# PWR-ORing_IC_2V_to_5V.net
KiCad netlist of a schematic drawn in Altium Designer
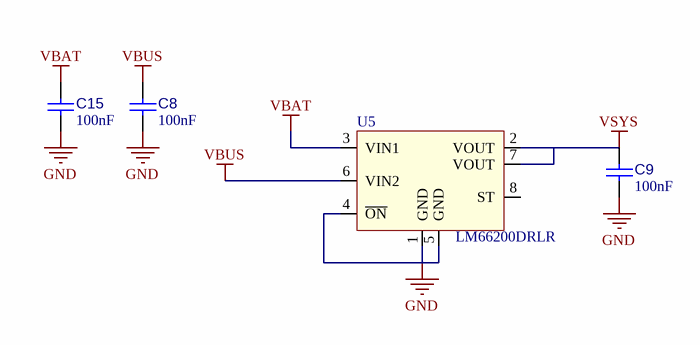
[diagram p0: PWR-ORing IC 2V to 5V.SchDoc]

(export (version "E")
  (design (tool "Eeschema 10.0.6"))
  (components
    (comp (ref "C8")
      (value "100nF")
      (footprint "C_1005[0402]")
      (description "Capacitor type 1")
      (fields (field (name "TOLERANCE") "10%") (field (name "Comment") "Cap 100nF 0402"))
      (libsource (lib "TEP_243-Altium_DBLib") (part "capacitor"))
    )
    (comp (ref "C9")
      (value "100nF")
      (footprint "C_1005[0402]")
      (description "Capacitor type 1")
      (fields (field (name "TOLERANCE") "10%") (field (name "Comment") "Cap 100nF 0402"))
      (libsource (lib "TEP_243-Altium_DBLib") (part "capacitor"))
    )
    (comp (ref "C15")
      (value "100nF")
      (footprint "C_1005[0402]")
      (description "Capacitor type 1")
      (fields (field (name "TOLERANCE") "10%") (field (name "Comment") "Cap 100nF 0402"))
      (libsource (lib "TEP_243-Altium_DBLib") (part "capacitor"))
    )
    (comp (ref "U5")
      (value "LM66200DRLR")
      (footprint "U_SOT583_50P210X120X60-8")
      (description "ORing Controller N-Channel 2:1 SOT-583")
      (libsource (lib "243-336_MP_Manette") (part "U_LM66200DRLR"))
    )
  )
  (nets
    (net (code "1") (name "GND") (class "Default")
      (node (ref "C15") (pin "1") (pinfunction "1_1") (pintype "passive"))
      (node (ref "C8") (pin "1") (pinfunction "1_1") (pintype "passive"))
      (node (ref "C9") (pin "1") (pinfunction "1_1") (pintype "passive"))
      (node (ref "U5") (pin "1") (pinfunction "GND_1") (pintype "power_in"))
      (node (ref "U5") (pin "4") (pinfunction "~{ON}_4") (pintype "passive"))
      (node (ref "U5") (pin "5") (pinfunction "GND_5") (pintype "power_in"))
    )
    (net (code "2") (name "VBAT") (class "Default")
      (node (ref "C15") (pin "2") (pinfunction "2_2") (pintype "passive"))
      (node (ref "U5") (pin "3") (pinfunction "VIN1_3") (pintype "power_in"))
    )
    (net (code "3") (name "VBUS") (class "Default")
      (node (ref "C8") (pin "2") (pinfunction "2_2") (pintype "passive"))
      (node (ref "U5") (pin "6") (pinfunction "VIN2_6") (pintype "power_in"))
    )
    (net (code "4") (name "VSYS") (class "Default")
      (node (ref "C9") (pin "2") (pinfunction "2_2") (pintype "passive"))
      (node (ref "U5") (pin "2") (pinfunction "VOUT_2") (pintype "power_in"))
      (node (ref "U5") (pin "7") (pinfunction "VOUT_7") (pintype "power_in"))
    )
    (net (code "5") (name "unconnected-(U5-ST-Pad8)") (class "Default")
      (node (ref "U5") (pin "8") (pinfunction "ST_8") (pintype "open_emitter"))
    )
  )
)
